# MD029A_Power.net
KiCad netlist of a schematic drawn in Altium Designer
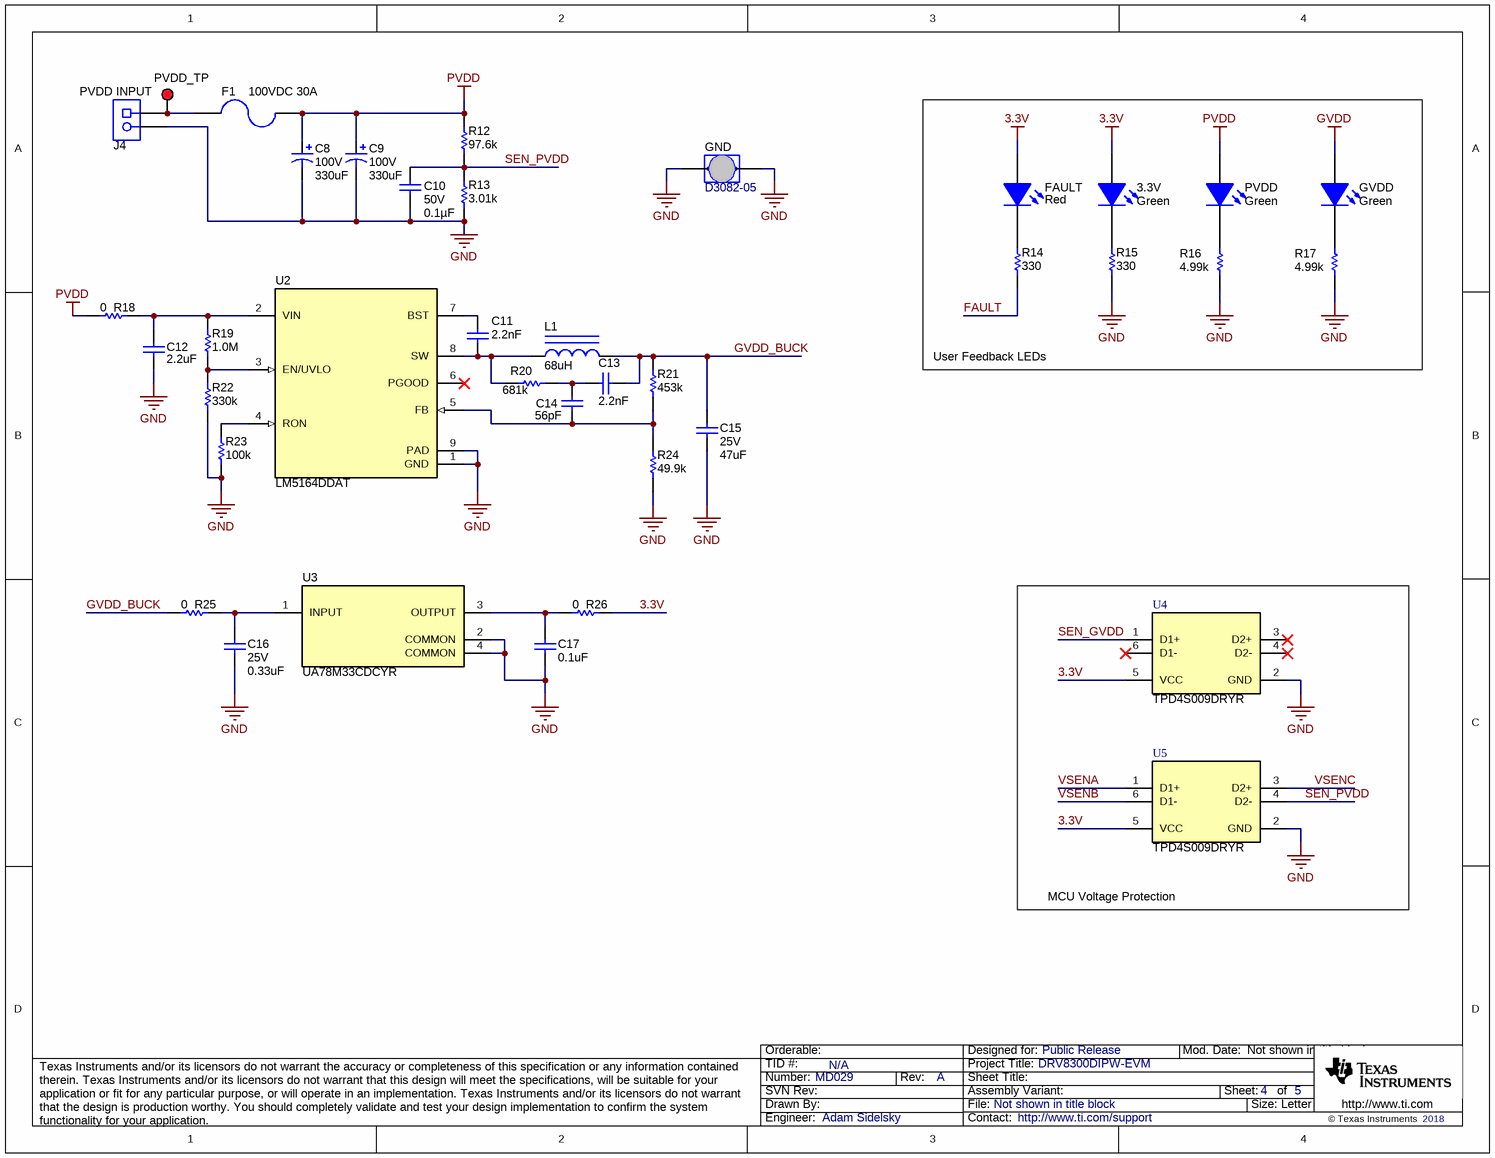
[diagram p0: MD029A_Power.SchDoc]

(export (version "E")
  (design (tool "Eeschema 10.0.6"))
  (components
    (comp (ref "3.3V")
      (value "Green")
      (footprint "LED_LTST-C171")
      (description "LED, Green, SMD")
      (fields (field (name "MANUFACTURER") "Lite-On") (field (name "PARTNUMBER") "LTST-C171GKT"))
      (libsource (lib "Altium Vault - TI") (part "CMP-0002830-3"))
    )
    (comp (ref "C8")
      (value "EEV-FK2A331M")
      (footprint "SM_RADIAL_K16")
      (description "CAP, AL, 330 uF, 100 V, +/- 20%, 0.153 ohm, AEC-Q200 Grade 2, SMD")
      (fields
        (field (name "MANUFACTURER") "Panasonic")
        (field (name "VDC_V") "100V")
        (field (name "VALUEDISPLAYED") "330uF")
        (field (name "PUBLISHER") "Texas Instruments")
      )
      (libsource (lib "Altium Vault - TI") (part "CMP-0011224-2"))
    )
    (comp (ref "C9")
      (value "EEV-FK2A331M")
      (footprint "SM_RADIAL_K16")
      (description "CAP, AL, 330 uF, 100 V, +/- 20%, 0.153 ohm, AEC-Q200 Grade 2, SMD")
      (fields
        (field (name "MANUFACTURER") "Panasonic")
        (field (name "VDC_V") "100V")
        (field (name "VALUEDISPLAYED") "330uF")
        (field (name "PUBLISHER") "Texas Instruments")
      )
      (libsource (lib "Altium Vault - TI") (part "Cap_Polarized"))
    )
    (comp (ref "C10")
      (value "C0603C104K5RACAUTO")
      (footprint "0603L")
      (description "CAP, CERM, 0.1 µF, 50 V,+/- 10%, X7R, AEC-Q200 Grade 1, 0603")
      (fields
        (field (name "MANUFACTURER") "Kemet")
        (field (name "VALUE2") "50V")
        (field (name "VALUEDISPLAYED") "0.1µF")
      )
      (libsource (lib "Altium Vault - TI") (part "Capacitor"))
    )
    (comp (ref "C11")
      (value "CGA3E2X7R2A222K080AA")
      (footprint "0603L")
      (description "CAP, CERM, 2200 pF, 100 V, +/- 10%, X7R, AEC-Q200 Grade 1, 0603")
      (fields
        (field (name "MANUFACTURER") "TDK")
        (field (name "CAP_F") "2.2nF")
        (field (name "PUBLISHER") "Texas Instruments")
      )
      (libsource (lib "Altium Vault - TI") (part "Capacitor"))
    )
    (comp (ref "C12")
      (value "C1210C225K1RACTU")
      (footprint "1210_210L")
      (description "CAP, CERM, 2.2 uF, 100 V, +/- 10%, X7R, 1210")
      (fields
        (field (name "MANUFACTURER") "Kemet")
        (field (name "VALUEDISPLAYED") "2.2uF")
        (field (name "PUBLISHER") "Texas Instruments")
      )
      (libsource (lib "Altium Vault - TI") (part "Capacitor"))
    )
    (comp (ref "C13")
      (value "CGA3E2X7R2A222K080AA")
      (footprint "0603L")
      (description "CAP, CERM, 2200 pF, 100 V, +/- 10%, X7R, AEC-Q200 Grade 1, 0603")
      (fields
        (field (name "MANUFACTURER") "TDK")
        (field (name "CAP_F") "2.2nF")
        (field (name "PUBLISHER") "Texas Instruments")
      )
      (libsource (lib "Altium Vault - TI") (part "Capacitor"))
    )
    (comp (ref "C14")
      (value "GRM1885C2A560JA01D")
      (footprint "0603L")
      (description "CAP, CERM, 56 pF, 100 V, +/- 5%, C0G/NP0, 0603")
      (fields
        (field (name "MANUFACTURER") "MuRata")
        (field (name "VALUEDISPLAYED") "56pF")
        (field (name "PUBLISHER") "Texas Instruments")
      )
      (libsource (lib "Altium Vault - TI") (part "Capacitor"))
    )
    (comp (ref "C15")
      (value "C3216JB1E476M160AC")
      (footprint "1206L")
      (description "CAP, CERM, 47 uF, 25 V, +/- 20%, JB, 1206")
      (fields
        (field (name "MANUFACTURER") "TDK")
        (field (name "VDC_V") "25V")
        (field (name "VALUEDISPLAYED") "47uF")
        (field (name "PUBLISHER") "Texas Instruments")
      )
      (libsource (lib "Altium Vault - TI") (part "Capacitor"))
    )
    (comp (ref "C16")
      (value "08053D334KAT2A")
      (footprint "0805L")
      (description "CAP, CERM, 0.33 uF, 25 V, +/- 10%, X5R, 0805")
      (fields
        (field (name "MANUFACTURER") "AVX")
        (field (name "VDC_V") "25V")
        (field (name "VALUEDISPLAYED") "0.33uF")
        (field (name "PUBLISHER") "Texas Instruments")
      )
      (libsource (lib "Altium Vault - TI") (part "Capacitor"))
    )
    (comp (ref "C17")
      (value "C0603C104J4RACTU")
      (footprint "0603L")
      (description "CAP, CERM, 0.1 uF, 16 V, +/- 5%, X7R, 0603")
      (fields
        (field (name "VALUEDISPLAYED") "0.1uF")
        (field (name "MANUFACTURER") "Kemet")
        (field (name "PUBLISHER") "Texas Instruments")
      )
      (libsource (lib "Altium Vault - TI") (part "CMP-0006857-4"))
    )
    (comp (ref "F1")
      (value "100VDC 30A")
      (footprint "Fuse_0463")
      (description "Fuse, 30 A, 250 VAC, 100 VDC, SMD")
      (fields (field (name "PARTNUMBER") "0463030.ER") (field (name "MANUFACTURER") "Littelfuse"))
      (libsource (lib "Altium Vault - TI") (part "CMP-0077200-3"))
    )
    (comp (ref "FAULT")
      (value "Red")
      (footprint "LED_LTST-C170_Red")
      (description "LED, Red, SMD")
      (fields (field (name "MANUFACTURER") "Lite-On") (field (name "PARTNUMBER") "LTST-C170KRKT"))
      (libsource (lib "Altium Vault - TI") (part "CMP-0002829-3"))
    )
    (comp (ref "GND")
      (value "D3082-05")
      (footprint "Harwin_D3082-05")
      (description "1mm Uninsulated Shorting Plug, 10.16mm spacing, TH")
      (fields (field (name "MANUFACTURER") "Harwin") (field (name "PUBLISHER") "Texas Instruments"))
      (libsource (lib "Altium Vault - TI") (part "Jumper_2p"))
    )
    (comp (ref "GVDD")
      (value "Green")
      (footprint "LED_LTST-C171")
      (description "LED, Green, SMD")
      (fields (field (name "MANUFACTURER") "Lite-On") (field (name "PARTNUMBER") "LTST-C171GKT"))
      (libsource (lib "Altium Vault - TI") (part "CMP-0002830-3"))
    )
    (comp (ref "J4")
      (value "PVDD INPUT")
      (footprint "Phoenix_1902547")
      (description "Terminal Block, 9.52mm, 2x1, R/A, TH")
      (fields
        (field (name "PARTNUMBER") "1902547")
        (field (name "MANUFACTURER") "Phoenix Contact")
        (field (name "PUBLISHER") "Texas Instruments")
      )
      (libsource (lib "Altium Vault - TI") (part "CMP-0055527-1"))
    )
    (comp (ref "L1")
      (value "SDR1006-680KL")
      (footprint "SDR1006")
      (description "Inductor, Drum Core, Ferrite, 68 uH, 1.1 A, 0.22 ohm, SMD")
      (fields
        (field (name "MANUFACTURER") "Bourns")
        (field (name "VALUEDISPLAYED") "68uH")
        (field (name "PUBLISHER") "Texas Instruments")
      )
      (libsource (lib "Altium Vault - TI") (part "Inductor_Iron"))
    )
    (comp (ref "PVDD")
      (value "Green")
      (footprint "LED_LTST-C171")
      (description "LED, Green, SMD")
      (fields (field (name "MANUFACTURER") "Lite-On") (field (name "PARTNUMBER") "LTST-C171GKT"))
      (libsource (lib "Altium Vault - TI") (part "CMP-0002830-3"))
    )
    (comp (ref "PVDD_TP")
      (value "5000")
      (footprint "Keystone5000")
      (description "Test Point, Miniature, Red, TH")
      (fields (field (name "MANUFACTURER") "Keystone") (field (name "PUBLISHER") "Texas Instruments"))
      (libsource (lib "Altium Vault - TI") (part "5000"))
    )
    (comp (ref "R12")
      (value "CRCW060397K6FKEA")
      (footprint "0603L")
      (description "RES, 97.6 k, 1%, 0.1 W, AEC-Q200 Grade 0, 0603")
      (fields (field (name "MANUFACTURER") "Vishay-Dale") (field (name "VALUEDISPLAYED") "97.6k"))
      (libsource (lib "Altium Vault - TI") (part "Resistor"))
    )
    (comp (ref "R13")
      (value "CRCW06033K01FKEA")
      (footprint "0603L")
      (description "RES, 3.01 k, 1%, 0.1 W, AEC-Q200 Grade 0, 0603")
      (fields (field (name "MANUFACTURER") "Vishay-Dale") (field (name "VALUEDISPLAYED") "3.01k"))
      (libsource (lib "Altium Vault - TI") (part "Resistor"))
    )
    (comp (ref "R14")
      (value "CRCW0603330RJNEA")
      (footprint "0603L")
      (description "RES, 330, 5%, 0.1 W, AEC-Q200 Grade 0, 0603")
      (fields (field (name "MANUFACTURER") "Vishay-Dale") (field (name "VALUEDISPLAYED") "330"))
      (libsource (lib "Altium Vault - TI") (part "CMP-0025785-4"))
    )
    (comp (ref "R15")
      (value "CRCW0603330RJNEA")
      (footprint "0603L")
      (description "RES, 330, 5%, 0.1 W, AEC-Q200 Grade 0, 0603")
      (fields (field (name "MANUFACTURER") "Vishay-Dale") (field (name "VALUEDISPLAYED") "330"))
      (libsource (lib "Altium Vault - TI") (part "CMP-0025785-4"))
    )
    (comp (ref "R16")
      (value "4.99k")
      (footprint "0603L")
      (description "RES, 4.99 k, 1%, 0.1 W, AEC-Q200 Grade 0, 0603")
      (fields (field (name "PARTNUMBER") "CRCW06034K99FKEA") (field (name "MANUFACTURER") "Vishay-Dale"))
      (libsource (lib "Altium Vault - TI") (part "Resistor"))
    )
    (comp (ref "R17")
      (value "4.99k")
      (footprint "0603L")
      (description "RES, 4.99 k, 1%, 0.1 W, AEC-Q200 Grade 0, 0603")
      (fields (field (name "PARTNUMBER") "CRCW06034K99FKEA") (field (name "MANUFACTURER") "Vishay-Dale"))
      (libsource (lib "Altium Vault - TI") (part "Resistor"))
    )
    (comp (ref "R18")
      (value "0")
      (footprint "0603L")
      (description "RES, 0, 5%, 0.1 W, AEC-Q200 Grade 0, 0603")
      (fields (field (name "PARTNUMBER") "CRCW06030000Z0EA") (field (name "MANUFACTURER") "Vishay-Dale"))
      (libsource (lib "Altium Vault - TI") (part "Resistor"))
    )
    (comp (ref "R19")
      (value "CRCW06031M00JNEA")
      (footprint "0603L")
      (description "RES, 1.0 M, 5%, 0.1 W, AEC-Q200 Grade 0, 0603")
      (fields (field (name "MANUFACTURER") "Vishay-Dale") (field (name "VALUEDISPLAYED") "1.0M"))
      (libsource (lib "Altium Vault - TI") (part "Resistor"))
    )
    (comp (ref "R20")
      (value "RC0603FR-07681KL")
      (footprint "0603L")
      (description "RES, 681 k, 1%, 0.1 W, 0603")
      (fields (field (name "MANUFACTURER") "Yageo") (field (name "VALUEDISPLAYED") "681k"))
      (libsource (lib "Altium Vault - TI") (part "Resistor"))
    )
    (comp (ref "R21")
      (value "RC0603FR-07453KL")
      (footprint "0603L")
      (description "RES, 453 k, 1%, 0.1 W, 0603")
      (fields (field (name "MANUFACTURER") "Yageo") (field (name "VALUEDISPLAYED") "453k"))
      (libsource (lib "Altium Vault - TI") (part "Resistor"))
    )
    (comp (ref "R22")
      (value "CRCW0603330KJNEA")
      (footprint "0603L")
      (description "RES, 330 k, 5%, 0.1 W, AEC-Q200 Grade 0, 0603")
      (fields (field (name "MANUFACTURER") "Vishay-Dale") (field (name "VALUEDISPLAYED") "330k"))
      (libsource (lib "Altium Vault - TI") (part "Resistor"))
    )
    (comp (ref "R23")
      (value "CRCW0402100KFKED")
      (footprint "0402L")
      (description "RES, 100 k, 1%, 0.063 W, AEC-Q200 Grade 0, 0402")
      (fields (field (name "MANUFACTURER") "Vishay-Dale") (field (name "VALUEDISPLAYED") "100k"))
      (libsource (lib "Altium Vault - TI") (part "Resistor"))
    )
    (comp (ref "R24")
      (value "RC0603FR-0749K9L")
      (footprint "0603L")
      (description "RES, 49.9 k, 1%, 0.1 W, 0603")
      (fields (field (name "MANUFACTURER") "Yageo") (field (name "VALUEDISPLAYED") "49.9k"))
      (libsource (lib "Altium Vault - TI") (part "Resistor"))
    )
    (comp (ref "R25")
      (value "0")
      (footprint "0603L")
      (description "RES, 0, 5%, 0.1 W, AEC-Q200 Grade 0, 0603")
      (fields (field (name "PARTNUMBER") "CRCW06030000Z0EA") (field (name "MANUFACTURER") "Vishay-Dale"))
      (libsource (lib "Altium Vault - TI") (part "Resistor"))
    )
    (comp (ref "R26")
      (value "0")
      (footprint "0603L")
      (description "RES, 0, 5%, 0.1 W, AEC-Q200 Grade 0, 0603")
      (fields (field (name "PARTNUMBER") "CRCW06030000Z0EA") (field (name "MANUFACTURER") "Vishay-Dale"))
      (libsource (lib "Altium Vault - TI") (part "Resistor"))
    )
    (comp (ref "U2")
      (value "LM5164DDAT")
      (footprint "DDA0008E_N")
      (description "100-V Low IQ Synchronous Buck Regulator, DDA0008E (SOIC-8)")
      (fields (field (name "MANUFACTURER") "Texas Instruments") (field (name "PARTNUMBER") "LM5164DDAT"))
      (libsource (lib "Altium Vault - TI") (part "LM5164"))
    )
    (comp (ref "U3")
      (value "UA78M33CDCYR")
      (footprint "DCY0004A_N")
      (description "500-mA, 25-V, Linear Voltage Regulators, DCY0004A (SOT-223-4)")
      (fields
        (field (name "ALTERNATE PARTNUMBER") "UA78M33CDCY")
        (field (name "MANUFACTURER") "Texas Instruments")
        (field (name "PARTNUMBER") "UA78M33CDCYR")
      )
      (libsource (lib "Altium Vault - TI") (part "UA78MXXDCY"))
    )
    (comp (ref "U4")
      (value "TPD4S009DRYR")
      (footprint "DRY0006A")
      (description "4-Channel ESD Solution for High-Speed Differential Interface, DRY0006A (USON-6)")
      (fields (field (name "MANUFACTURER") "Texas Instruments") (field (name "PARTNUMBER") "TPD4S009DRYR"))
      (libsource (lib "Altium Vault - TI") (part "TI-TPD4S009-SON_DRY-6"))
    )
    (comp (ref "U5")
      (value "TPD4S009DRYR")
      (footprint "DRY0006A")
      (description "4-Channel ESD Solution for High-Speed Differential Interface, DRY0006A (USON-6)")
      (fields (field (name "MANUFACTURER") "Texas Instruments") (field (name "PARTNUMBER") "TPD4S009DRYR"))
      (libsource (lib "Altium Vault - TI") (part "TI-TPD4S009-SON_DRY-6"))
    )
  )
  (nets
    (net (code "1") (name "/FAULT") (class "Default")
      (node (ref "R14") (pin "1") (pinfunction "1_1") (pintype "passive"))
    )
    (net (code "2") (name "/GVDD_BUCK") (class "Default")
      (node (ref "C13") (pin "1") (pinfunction "1_1") (pintype "passive"))
      (node (ref "C15") (pin "1") (pinfunction "1_1") (pintype "passive"))
      (node (ref "L1") (pin "2") (pinfunction "2_2") (pintype "passive"))
      (node (ref "R21") (pin "2") (pinfunction "2_2") (pintype "passive"))
      (node (ref "R25") (pin "1") (pinfunction "1_1") (pintype "passive"))
    )
    (net (code "3") (name "/SEN_GVDD") (class "Default")
      (node (ref "U4") (pin "1") (pinfunction "D1+_1") (pintype "passive"))
    )
    (net (code "4") (name "/SEN_PVDD") (class "Default")
      (node (ref "C10") (pin "2") (pinfunction "2_2") (pintype "passive"))
      (node (ref "R12") (pin "1") (pinfunction "1_1") (pintype "passive"))
      (node (ref "R13") (pin "2") (pinfunction "2_2") (pintype "passive"))
      (node (ref "U5") (pin "4") (pinfunction "D2-_4") (pintype "passive"))
    )
    (net (code "5") (name "/VSENA") (class "Default")
      (node (ref "U5") (pin "1") (pinfunction "D1+_1") (pintype "passive"))
    )
    (net (code "6") (name "/VSENB") (class "Default")
      (node (ref "U5") (pin "6") (pinfunction "D1-_6") (pintype "passive"))
    )
    (net (code "7") (name "/VSENC") (class "Default")
      (node (ref "U5") (pin "3") (pinfunction "D2+_3") (pintype "passive"))
    )
    (net (code "8") (name "3.3V") (class "Default")
      (node (ref "3.3V") (pin "1") (pinfunction "A_1") (pintype "passive"))
      (node (ref "FAULT") (pin "1") (pinfunction "A_1") (pintype "passive"))
      (node (ref "R26") (pin "2") (pinfunction "2_2") (pintype "passive"))
      (node (ref "U4") (pin "5") (pinfunction "VCC_5") (pintype "power_in"))
      (node (ref "U5") (pin "5") (pinfunction "VCC_5") (pintype "power_in"))
    )
    (net (code "9") (name "GND") (class "Default")
      (node (ref "C10") (pin "1") (pinfunction "1_1") (pintype "passive"))
      (node (ref "C12") (pin "2") (pinfunction "2_2") (pintype "passive"))
      (node (ref "C15") (pin "2") (pinfunction "2_2") (pintype "passive"))
      (node (ref "C16") (pin "2") (pinfunction "2_2") (pintype "passive"))
      (node (ref "C17") (pin "2") (pinfunction "2_2") (pintype "passive"))
      (node (ref "C8") (pin "2") (pinfunction "-_2") (pintype "passive"))
      (node (ref "C9") (pin "2") (pinfunction "-_2") (pintype "passive"))
      (node (ref "GND") (pin "1") (pinfunction "1_1") (pintype "passive"))
      (node (ref "GND") (pin "2") (pinfunction "2_2") (pintype "passive"))
      (node (ref "J4") (pin "2") (pinfunction "2_2") (pintype "passive"))
      (node (ref "R13") (pin "1") (pinfunction "1_1") (pintype "passive"))
      (node (ref "R15") (pin "1") (pinfunction "1_1") (pintype "passive"))
      (node (ref "R16") (pin "1") (pinfunction "1_1") (pintype "passive"))
      (node (ref "R17") (pin "1") (pinfunction "1_1") (pintype "passive"))
      (node (ref "R22") (pin "1") (pinfunction "1_1") (pintype "passive"))
      (node (ref "R23") (pin "1") (pinfunction "1_1") (pintype "passive"))
      (node (ref "R24") (pin "1") (pinfunction "1_1") (pintype "passive"))
      (node (ref "U2") (pin "1") (pinfunction "GND_1") (pintype "power_in"))
      (node (ref "U2") (pin "9") (pinfunction "PAD_9") (pintype "passive"))
      (node (ref "U3") (pin "2") (pinfunction "COMMON_2") (pintype "power_in"))
      (node (ref "U3") (pin "4") (pinfunction "COMMON_4") (pintype "power_in"))
      (node (ref "U4") (pin "2") (pinfunction "GND_2") (pintype "power_in"))
      (node (ref "U5") (pin "2") (pinfunction "GND_2") (pintype "power_in"))
    )
    (net (code "10") (name "GVDD") (class "Default")
      (node (ref "GVDD") (pin "1") (pinfunction "A_1") (pintype "passive"))
    )
    (net (code "11") (name "Net-(3.3V-K)") (class "Default")
      (node (ref "3.3V") (pin "2") (pinfunction "K_2") (pintype "passive"))
      (node (ref "R15") (pin "2") (pinfunction "2_2") (pintype "passive"))
    )
    (net (code "12") (name "Net-(C13-Pad2)") (class "Default")
      (node (ref "C13") (pin "2") (pinfunction "2_2") (pintype "passive"))
      (node (ref "C14") (pin "1") (pinfunction "1_1") (pintype "passive"))
      (node (ref "R20") (pin "2") (pinfunction "2_2") (pintype "passive"))
    )
    (net (code "13") (name "Net-(F1-Pad2)") (class "Default")
      (node (ref "F1") (pin "2") (pinfunction "2_2") (pintype "passive"))
      (node (ref "J4") (pin "1") (pinfunction "1_1") (pintype "passive"))
      (node (ref "PVDD_TP") (pin "1") (pintype "passive"))
    )
    (net (code "14") (name "Net-(FAULT-K)") (class "Default")
      (node (ref "FAULT") (pin "2") (pinfunction "K_2") (pintype "passive"))
      (node (ref "R14") (pin "2") (pinfunction "2_2") (pintype "passive"))
    )
    (net (code "15") (name "Net-(GVDD-K)") (class "Default")
      (node (ref "GVDD") (pin "2") (pinfunction "K_2") (pintype "passive"))
      (node (ref "R17") (pin "2") (pinfunction "2_2") (pintype "passive"))
    )
    (net (code "16") (name "Net-(PVDD-K)") (class "Default")
      (node (ref "PVDD") (pin "2") (pinfunction "K_2") (pintype "passive"))
      (node (ref "R16") (pin "2") (pinfunction "2_2") (pintype "passive"))
    )
    (net (code "17") (name "Net-(U2-BST)") (class "Default")
      (node (ref "C11") (pin "1") (pinfunction "1_1") (pintype "passive"))
      (node (ref "U2") (pin "7") (pinfunction "BST_7") (pintype "power_in"))
    )
    (net (code "18") (name "Net-(U2-EN{slash}UVLO)") (class "Default")
      (node (ref "R19") (pin "1") (pinfunction "1_1") (pintype "passive"))
      (node (ref "R22") (pin "2") (pinfunction "2_2") (pintype "passive"))
      (node (ref "U2") (pin "3") (pinfunction "EN/UVLO_3") (pintype "input"))
    )
    (net (code "19") (name "Net-(U2-FB)") (class "Default")
      (node (ref "C14") (pin "2") (pinfunction "2_2") (pintype "passive"))
      (node (ref "R21") (pin "1") (pinfunction "1_1") (pintype "passive"))
      (node (ref "R24") (pin "2") (pinfunction "2_2") (pintype "passive"))
      (node (ref "U2") (pin "5") (pinfunction "FB_5") (pintype "input"))
    )
    (net (code "20") (name "Net-(U2-RON)") (class "Default")
      (node (ref "R23") (pin "2") (pinfunction "2_2") (pintype "passive"))
      (node (ref "U2") (pin "4") (pinfunction "RON_4") (pintype "input"))
    )
    (net (code "21") (name "Net-(U2-SW)") (class "Default")
      (node (ref "C11") (pin "2") (pinfunction "2_2") (pintype "passive"))
      (node (ref "L1") (pin "1") (pinfunction "1_1") (pintype "passive"))
      (node (ref "R20") (pin "1") (pinfunction "1_1") (pintype "passive"))
      (node (ref "U2") (pin "8") (pinfunction "SW_8") (pintype "power_in"))
    )
    (net (code "22") (name "Net-(U2-VIN)") (class "Default")
      (node (ref "C12") (pin "1") (pinfunction "1_1") (pintype "passive"))
      (node (ref "R18") (pin "2") (pinfunction "2_2") (pintype "passive"))
      (node (ref "R19") (pin "2") (pinfunction "2_2") (pintype "passive"))
      (node (ref "U2") (pin "2") (pinfunction "VIN_2") (pintype "power_in"))
    )
    (net (code "23") (name "Net-(U3-INPUT)") (class "Default")
      (node (ref "C16") (pin "1") (pinfunction "1_1") (pintype "passive"))
      (node (ref "R25") (pin "2") (pinfunction "2_2") (pintype "passive"))
      (node (ref "U3") (pin "1") (pinfunction "INPUT_1") (pintype "power_in"))
    )
    (net (code "24") (name "Net-(U3-OUTPUT)") (class "Default")
      (node (ref "C17") (pin "1") (pinfunction "1_1") (pintype "passive"))
      (node (ref "R26") (pin "1") (pinfunction "1_1") (pintype "passive"))
      (node (ref "U3") (pin "3") (pinfunction "OUTPUT_3") (pintype "power_in"))
    )
    (net (code "25") (name "PVDD") (class "Default")
      (node (ref "C8") (pin "1") (pinfunction "+_1") (pintype "passive"))
      (node (ref "C9") (pin "1") (pinfunction "+_1") (pintype "passive"))
      (node (ref "F1") (pin "1") (pinfunction "1_1") (pintype "passive"))
      (node (ref "PVDD") (pin "1") (pinfunction "A_1") (pintype "passive"))
      (node (ref "R12") (pin "2") (pinfunction "2_2") (pintype "passive"))
      (node (ref "R18") (pin "1") (pinfunction "1_1") (pintype "passive"))
    )
    (net (code "26") (name "unconnected-(U2-PGOOD-Pad6)") (class "Default")
      (node (ref "U2") (pin "6") (pinfunction "PGOOD_6") (pintype "open_collector+no_connect"))
    )
    (net (code "27") (name "unconnected-(U4-D1--Pad6)") (class "Default")
      (node (ref "U4") (pin "6") (pinfunction "D1-_6") (pintype "passive+no_connect"))
    )
    (net (code "28") (name "unconnected-(U4-D2+-Pad3)") (class "Default")
      (node (ref "U4") (pin "3") (pinfunction "D2+_3") (pintype "passive+no_connect"))
    )
    (net (code "29") (name "unconnected-(U4-D2--Pad4)") (class "Default")
      (node (ref "U4") (pin "4") (pinfunction "D2-_4") (pintype "passive+no_connect"))
    )
  )
)
